# Relay.net
KiCad netlist of a schematic drawn in Altium Designer
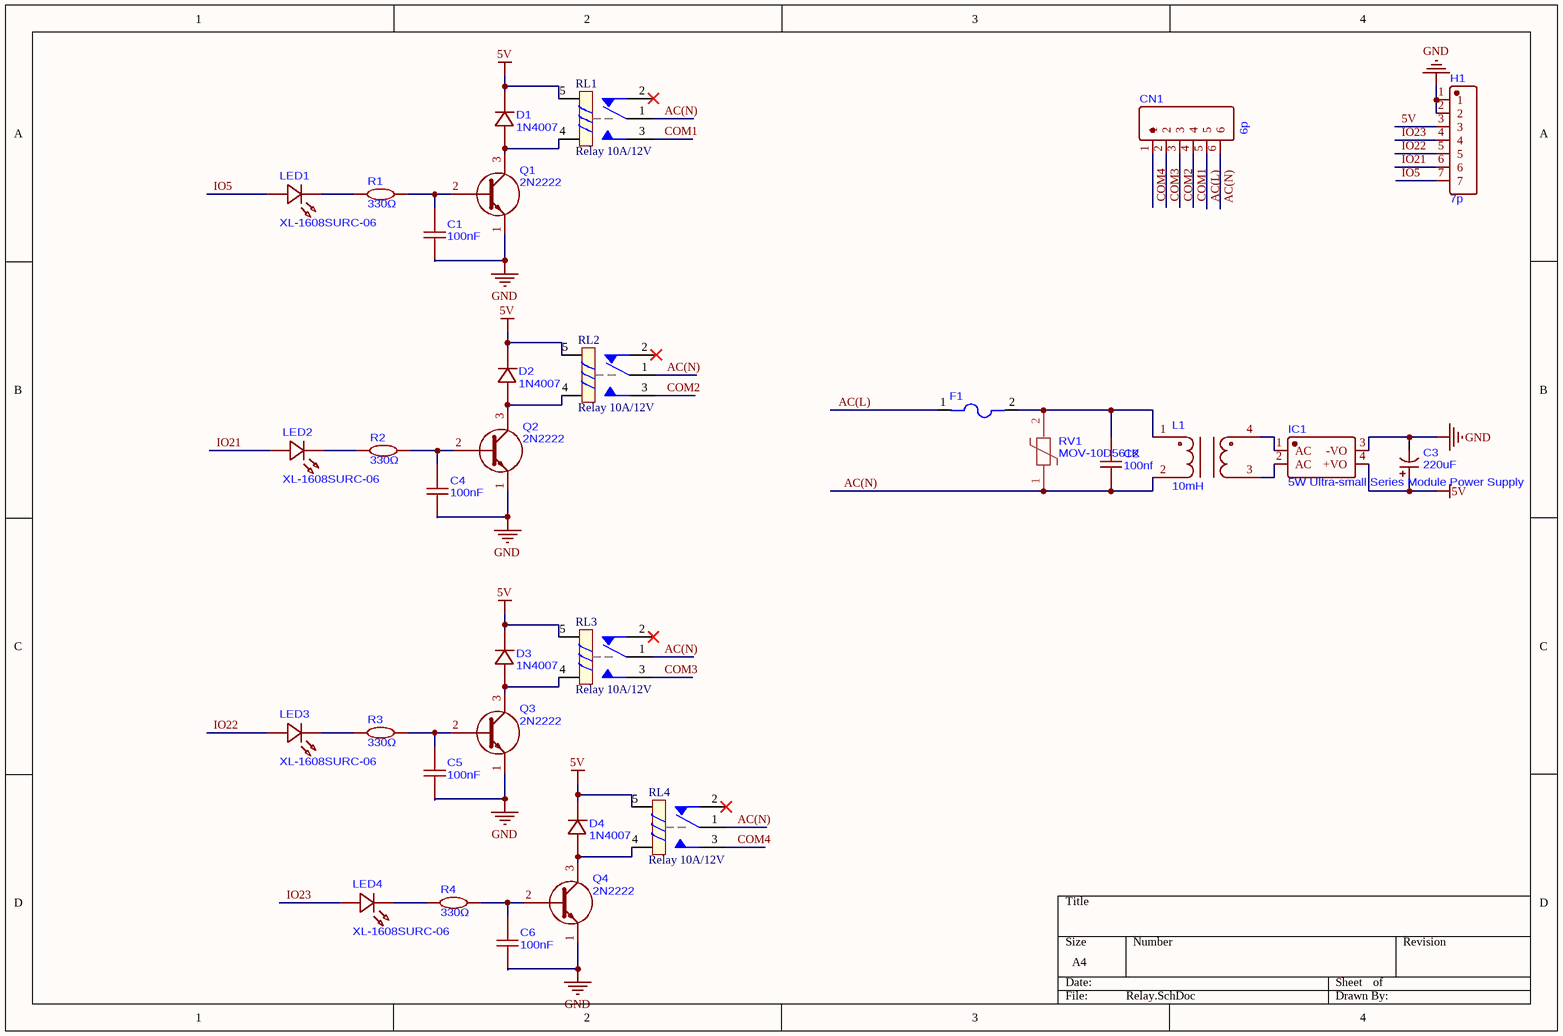
[diagram p0: Relay.SchDoc]

(export (version "E")
  (design (tool "Eeschema 10.0.6"))
  (components
    (comp (ref "C1")
      (value "100nF")
      (footprint "C0603")
      (description "50V 100nF X7R ±10% 0603 Ceramic Capacitors ROHS")
      (libsource (lib "Schlib2") (part "CC0603KRX7R9BB104"))
    )
    (comp (ref "C2")
      (value "100nf")
      (footprint "CAP-TH_L10.0-W5.0-P7.50-D0.6")
      (description "275V 100nF X2 ±10% Through Hole,P=7.5mm Ceramic Capacitors ROHS")
      (libsource (lib "Schlib2") (part "100nF"))
    )
    (comp (ref "C3")
      (value "220uF")
      (footprint "CAP-SMD_BD6.3-L6.6-W6.6-FD")
      (libsource (lib "cap220uF-10V") (part "RVT220UF10V67RV0037"))
    )
    (comp (ref "C4")
      (value "100nF")
      (footprint "C0603")
      (description "50V 100nF X7R ±10% 0603 Ceramic Capacitors ROHS")
      (libsource (lib "Schlib2") (part "CC0603KRX7R9BB104"))
    )
    (comp (ref "C5")
      (value "100nF")
      (footprint "C0603")
      (description "50V 100nF X7R ±10% 0603 Ceramic Capacitors ROHS")
      (libsource (lib "Schlib2") (part "CC0603KRX7R9BB104"))
    )
    (comp (ref "C6")
      (value "100nF")
      (footprint "C0603")
      (description "50V 100nF X7R ±10% 0603 Ceramic Capacitors ROHS")
      (libsource (lib "Schlib2") (part "CC0603KRX7R9BB104"))
    )
    (comp (ref "CN1")
      (value "6p")
      (footprint "CONN-TH_6P-MX128-5.08-GN01-06P-CU-Y-A")
      (libsource (lib "Schlib2") (part "MX128-5.08-GN01-06P-CU-Y-A"))
    )
    (comp (ref "D1")
      (value "1N4007")
      (footprint "DO-41_BD2.4-L4.7-P8.70-D0.9-RD")
      (description "30A 1kV 1.1V@1A 1A DO-41 Single Diodes ROHS")
      (libsource (lib "Schlib2") (part "1N4007"))
    )
    (comp (ref "D2")
      (value "1N4007")
      (footprint "DO-41_BD2.4-L4.7-P8.70-D0.9-RD")
      (description "30A 1kV 1.1V@1A 1A DO-41 Single Diodes ROHS")
      (libsource (lib "Schlib2") (part "1N4007"))
    )
    (comp (ref "D3")
      (value "1N4007")
      (footprint "DO-41_BD2.4-L4.7-P8.70-D0.9-RD")
      (description "30A 1kV 1.1V@1A 1A DO-41 Single Diodes ROHS")
      (libsource (lib "Schlib2") (part "1N4007"))
    )
    (comp (ref "D4")
      (value "1N4007")
      (footprint "DO-41_BD2.4-L4.7-P8.70-D0.9-RD")
      (description "30A 1kV 1.1V@1A 1A DO-41 Single Diodes ROHS")
      (libsource (lib "Schlib2") (part "1N4007"))
    )
    (comp (ref "F1")
      (value "FUSE BRD MNT 1A 250VAC/VDC 2410")
      (footprint "F2410")
      (description "50A Surface Mount Fuse 1A 2410 Fuses ROHS")
      (libsource (lib "Schlib2") (part "JFC2410-1100TS"))
    )
    (comp (ref "H1")
      (value "7p")
      (footprint "CONN-TH_7P-P2.54_XH2.54-7P")
      (libsource (lib "Schlib2") (part "WAFER-XH2.54-7PZZ"))
    )
    (comp (ref "IC1")
      (value "5W Ultra-small Series Module Power Supply")
      (footprint "PWRM-TH_HLK-5M05")
      (description "AC/DC-DC DIP,38x23mm AC DC Converters ROHS")
      (libsource (lib "Schlib2") (part "HLK-5M05"))
    )
    (comp (ref "L1")
      (value "10mH")
      (footprint "FILTER-TH_UU9.8Y-10MH")
      (description "10mH@1kHz 1.2Ω 2 Through Hole Common Mode Chokes ROHS")
      (libsource (lib "Schlib2") (part "UU9.8Y-10MH"))
    )
    (comp (ref "LED1")
      (value "XL-1608SURC-06")
      (footprint "LED0603-RD_RED")
      (description "20mA 2.3V Red 50mW 0603 LED Indication - Discrete ROHS")
      (libsource (lib "Schlib2") (part "XL-1608SURC-06"))
    )
    (comp (ref "LED2")
      (value "XL-1608SURC-06")
      (footprint "LED0603-RD_RED")
      (description "20mA 2.3V Red 50mW 0603 LED Indication - Discrete ROHS")
      (libsource (lib "Schlib2") (part "XL-1608SURC-06"))
    )
    (comp (ref "LED3")
      (value "XL-1608SURC-06")
      (footprint "LED0603-RD_RED")
      (description "20mA 2.3V Red 50mW 0603 LED Indication - Discrete ROHS")
      (libsource (lib "Schlib2") (part "XL-1608SURC-06"))
    )
    (comp (ref "LED4")
      (value "XL-1608SURC-06")
      (footprint "LED0603-RD_RED")
      (description "20mA 2.3V Red 50mW 0603 LED Indication - Discrete ROHS")
      (libsource (lib "Schlib2") (part "XL-1608SURC-06"))
    )
    (comp (ref "Q1")
      (value "2N2222")
      (footprint "2N2222")
      (description "625mW 40V 40@500mA,10V 600mA NPN TO-92 Single Bipolar Transistors ROHS")
      (libsource (lib "Schlib2") (part "2N2222A"))
    )
    (comp (ref "Q2")
      (value "2N2222")
      (footprint "2N2222")
      (description "625mW 40V 40@500mA,10V 600mA NPN TO-92 Single Bipolar Transistors ROHS")
      (libsource (lib "Schlib2") (part "2N2222A"))
    )
    (comp (ref "Q3")
      (value "2N2222")
      (footprint "2N2222")
      (description "625mW 40V 40@500mA,10V 600mA NPN TO-92 Single Bipolar Transistors ROHS")
      (libsource (lib "Schlib2") (part "2N2222A"))
    )
    (comp (ref "Q4")
      (value "2N2222")
      (footprint "2N2222")
      (description "625mW 40V 40@500mA,10V 600mA NPN TO-92 Single Bipolar Transistors ROHS")
      (libsource (lib "Schlib2") (part "2N2222A"))
    )
    (comp (ref "R1")
      (value "330Ω")
      (footprint "R0603")
      (description "100mW 330Ω 75V ±100ppm/℃ Thick Film Resistor ±1% 0603 Chip Resistor - Surface Mount ROHS")
      (libsource (lib "Schlib2") (part "RC0603FR-07330RL"))
    )
    (comp (ref "R2")
      (value "330Ω")
      (footprint "R0603")
      (description "100mW 330Ω 75V ±100ppm/℃ Thick Film Resistor ±1% 0603 Chip Resistor - Surface Mount ROHS")
      (libsource (lib "Schlib2") (part "RC0603FR-07330RL"))
    )
    (comp (ref "R3")
      (value "330Ω")
      (footprint "R0603")
      (description "100mW 330Ω 75V ±100ppm/℃ Thick Film Resistor ±1% 0603 Chip Resistor - Surface Mount ROHS")
      (libsource (lib "Schlib2") (part "RC0603FR-07330RL"))
    )
    (comp (ref "R4")
      (value "330Ω")
      (footprint "R0603")
      (description "100mW 330Ω 75V ±100ppm/℃ Thick Film Resistor ±1% 0603 Chip Resistor - Surface Mount ROHS")
      (libsource (lib "Schlib2") (part "RC0603FR-07330RL"))
    )
    (comp (ref "RL1")
      (value "Relay 10A/12V")
      (footprint "RL_10A_5V")
      (description "Relay SPDT,10A - 5VDC 5 Pin")
      (libsource (lib "Schlib2") (part "Relay 1"))
    )
    (comp (ref "RL2")
      (value "Relay 10A/12V")
      (footprint "RL_10A_5V")
      (description "Relay SPDT,10A - 5VDC 5 Pin")
      (libsource (lib "Schlib2") (part "Relay 1"))
    )
    (comp (ref "RL3")
      (value "Relay 10A/12V")
      (footprint "RL_10A_5V")
      (description "Relay SPDT,10A - 5VDC 5 Pin")
      (libsource (lib "Schlib2") (part "Relay 1"))
    )
    (comp (ref "RL4")
      (value "Relay 10A/12V")
      (footprint "RL_10A_5V")
      (description "Relay SPDT,10A - 5VDC 5 Pin")
      (libsource (lib "Schlib2") (part "Relay 1"))
    )
    (comp (ref "RV1")
      (value "MOV-10D561K")
      (footprint "MOV10D561K")
      (description "925V 460V 350V 560V Through Hole,P=7.5mm Varistors, MOVs ROHS")
      (libsource (lib "Schlib2") (part "MOV-10D561K"))
    )
  )
  (nets
    (net (code "1") (name "/AC(L)") (class "Default")
      (node (ref "CN1") (pin "5") (pinfunction "5_5") (pintype "passive"))
      (node (ref "F1") (pin "1") (pinfunction "1_1") (pintype "passive"))
    )
    (net (code "2") (name "/AC(N)") (class "Default")
      (node (ref "C2") (pin "2") (pinfunction "2_2") (pintype "passive"))
      (node (ref "CN1") (pin "6") (pinfunction "6_6") (pintype "passive"))
      (node (ref "L1") (pin "2") (pinfunction "2_2") (pintype "passive"))
      (node (ref "RL1") (pin "1") (pinfunction "1_1") (pintype "passive"))
      (node (ref "RL2") (pin "1") (pinfunction "1_1") (pintype "passive"))
      (node (ref "RL3") (pin "1") (pinfunction "1_1") (pintype "passive"))
      (node (ref "RL4") (pin "1") (pinfunction "1_1") (pintype "passive"))
      (node (ref "RV1") (pin "1") (pinfunction "1_1") (pintype "passive"))
    )
    (net (code "3") (name "/COM1") (class "Default")
      (node (ref "CN1") (pin "4") (pinfunction "4_4") (pintype "passive"))
      (node (ref "RL1") (pin "3") (pinfunction "3_3") (pintype "passive"))
    )
    (net (code "4") (name "/COM2") (class "Default")
      (node (ref "CN1") (pin "3") (pinfunction "3_3") (pintype "passive"))
      (node (ref "RL2") (pin "3") (pinfunction "3_3") (pintype "passive"))
    )
    (net (code "5") (name "/COM3") (class "Default")
      (node (ref "CN1") (pin "2") (pinfunction "2_2") (pintype "passive"))
      (node (ref "RL3") (pin "3") (pinfunction "3_3") (pintype "passive"))
    )
    (net (code "6") (name "/COM4") (class "Default")
      (node (ref "CN1") (pin "1") (pinfunction "1_1") (pintype "passive"))
      (node (ref "RL4") (pin "3") (pinfunction "3_3") (pintype "passive"))
    )
    (net (code "7") (name "/IO5") (class "Default")
      (node (ref "H1") (pin "7") (pinfunction "7_7") (pintype "passive"))
      (node (ref "LED1") (pin "2") (pinfunction "A_2") (pintype "passive"))
    )
    (net (code "8") (name "/IO21") (class "Default")
      (node (ref "H1") (pin "6") (pinfunction "6_6") (pintype "passive"))
      (node (ref "LED2") (pin "2") (pinfunction "A_2") (pintype "passive"))
    )
    (net (code "9") (name "/IO22") (class "Default")
      (node (ref "H1") (pin "5") (pinfunction "5_5") (pintype "passive"))
      (node (ref "LED3") (pin "2") (pinfunction "A_2") (pintype "passive"))
    )
    (net (code "10") (name "/IO23") (class "Default")
      (node (ref "H1") (pin "4") (pinfunction "4_4") (pintype "passive"))
      (node (ref "LED4") (pin "2") (pinfunction "A_2") (pintype "passive"))
    )
    (net (code "11") (name "5V") (class "Default")
      (node (ref "C3") (pin "1") (pinfunction "1_1") (pintype "passive"))
      (node (ref "D1") (pin "1") (pinfunction "K_1") (pintype "passive"))
      (node (ref "D2") (pin "1") (pinfunction "K_1") (pintype "passive"))
      (node (ref "D3") (pin "1") (pinfunction "K_1") (pintype "passive"))
      (node (ref "D4") (pin "1") (pinfunction "K_1") (pintype "passive"))
      (node (ref "H1") (pin "3") (pinfunction "3_3") (pintype "passive"))
      (node (ref "IC1") (pin "4") (pinfunction "+VO_4") (pintype "passive"))
      (node (ref "RL1") (pin "5") (pinfunction "5_5") (pintype "passive"))
      (node (ref "RL2") (pin "5") (pinfunction "5_5") (pintype "passive"))
      (node (ref "RL3") (pin "5") (pinfunction "5_5") (pintype "passive"))
      (node (ref "RL4") (pin "5") (pinfunction "5_5") (pintype "passive"))
    )
    (net (code "12") (name "GND") (class "Default")
      (node (ref "C1") (pin "1") (pinfunction "1_1") (pintype "passive"))
      (node (ref "C3") (pin "2") (pinfunction "2_2") (pintype "passive"))
      (node (ref "C4") (pin "1") (pinfunction "1_1") (pintype "passive"))
      (node (ref "C5") (pin "1") (pinfunction "1_1") (pintype "passive"))
      (node (ref "C6") (pin "1") (pinfunction "1_1") (pintype "passive"))
      (node (ref "H1") (pin "1") (pinfunction "1_1") (pintype "passive"))
      (node (ref "H1") (pin "2") (pinfunction "2_2") (pintype "passive"))
      (node (ref "IC1") (pin "3") (pinfunction "-VO_3") (pintype "passive"))
      (node (ref "Q1") (pin "1") (pintype "passive"))
      (node (ref "Q2") (pin "1") (pintype "passive"))
      (node (ref "Q3") (pin "1") (pintype "passive"))
      (node (ref "Q4") (pin "1") (pintype "passive"))
    )
    (net (code "13") (name "Net-(C1-Pad2)") (class "Default")
      (node (ref "C1") (pin "2") (pinfunction "2_2") (pintype "passive"))
      (node (ref "Q1") (pin "2") (pintype "passive"))
      (node (ref "R1") (pin "2") (pinfunction "2_2") (pintype "passive"))
    )
    (net (code "14") (name "Net-(C2-Pad1)") (class "Default")
      (node (ref "C2") (pin "1") (pinfunction "1_1") (pintype "passive"))
      (node (ref "F1") (pin "2") (pinfunction "2_2") (pintype "passive"))
      (node (ref "L1") (pin "1") (pinfunction "1_1") (pintype "passive"))
      (node (ref "RV1") (pin "2") (pinfunction "2_2") (pintype "passive"))
    )
    (net (code "15") (name "Net-(C4-Pad2)") (class "Default")
      (node (ref "C4") (pin "2") (pinfunction "2_2") (pintype "passive"))
      (node (ref "Q2") (pin "2") (pintype "passive"))
      (node (ref "R2") (pin "2") (pinfunction "2_2") (pintype "passive"))
    )
    (net (code "16") (name "Net-(C5-Pad2)") (class "Default")
      (node (ref "C5") (pin "2") (pinfunction "2_2") (pintype "passive"))
      (node (ref "Q3") (pin "2") (pintype "passive"))
      (node (ref "R3") (pin "2") (pinfunction "2_2") (pintype "passive"))
    )
    (net (code "17") (name "Net-(C6-Pad2)") (class "Default")
      (node (ref "C6") (pin "2") (pinfunction "2_2") (pintype "passive"))
      (node (ref "Q4") (pin "2") (pintype "passive"))
      (node (ref "R4") (pin "2") (pinfunction "2_2") (pintype "passive"))
    )
    (net (code "18") (name "Net-(D1-A)") (class "Default")
      (node (ref "D1") (pin "2") (pinfunction "A_2") (pintype "passive"))
      (node (ref "Q1") (pin "3") (pintype "passive"))
      (node (ref "RL1") (pin "4") (pinfunction "4_4") (pintype "passive"))
    )
    (net (code "19") (name "Net-(D2-A)") (class "Default")
      (node (ref "D2") (pin "2") (pinfunction "A_2") (pintype "passive"))
      (node (ref "Q2") (pin "3") (pintype "passive"))
      (node (ref "RL2") (pin "4") (pinfunction "4_4") (pintype "passive"))
    )
    (net (code "20") (name "Net-(D3-A)") (class "Default")
      (node (ref "D3") (pin "2") (pinfunction "A_2") (pintype "passive"))
      (node (ref "Q3") (pin "3") (pintype "passive"))
      (node (ref "RL3") (pin "4") (pinfunction "4_4") (pintype "passive"))
    )
    (net (code "21") (name "Net-(D4-A)") (class "Default")
      (node (ref "D4") (pin "2") (pinfunction "A_2") (pintype "passive"))
      (node (ref "Q4") (pin "3") (pintype "passive"))
      (node (ref "RL4") (pin "4") (pinfunction "4_4") (pintype "passive"))
    )
    (net (code "22") (name "Net-(IC1-AC-Pad1)") (class "Default")
      (node (ref "IC1") (pin "1") (pinfunction "AC_1") (pintype "passive"))
      (node (ref "L1") (pin "4") (pinfunction "4_4") (pintype "passive"))
    )
    (net (code "23") (name "Net-(IC1-AC-Pad2)") (class "Default")
      (node (ref "IC1") (pin "2") (pinfunction "AC_2") (pintype "passive"))
      (node (ref "L1") (pin "3") (pinfunction "3_3") (pintype "passive"))
    )
    (net (code "24") (name "Net-(LED1-K)") (class "Default")
      (node (ref "LED1") (pin "1") (pinfunction "K_1") (pintype "passive"))
      (node (ref "R1") (pin "1") (pinfunction "1_1") (pintype "passive"))
    )
    (net (code "25") (name "Net-(LED2-K)") (class "Default")
      (node (ref "LED2") (pin "1") (pinfunction "K_1") (pintype "passive"))
      (node (ref "R2") (pin "1") (pinfunction "1_1") (pintype "passive"))
    )
    (net (code "26") (name "Net-(LED3-K)") (class "Default")
      (node (ref "LED3") (pin "1") (pinfunction "K_1") (pintype "passive"))
      (node (ref "R3") (pin "1") (pinfunction "1_1") (pintype "passive"))
    )
    (net (code "27") (name "Net-(LED4-K)") (class "Default")
      (node (ref "LED4") (pin "1") (pinfunction "K_1") (pintype "passive"))
      (node (ref "R4") (pin "1") (pinfunction "1_1") (pintype "passive"))
    )
    (net (code "28") (name "unconnected-(RL1-Pad2)") (class "Default")
      (node (ref "RL1") (pin "2") (pinfunction "2_2") (pintype "passive+no_connect"))
    )
    (net (code "29") (name "unconnected-(RL2-Pad2)") (class "Default")
      (node (ref "RL2") (pin "2") (pinfunction "2_2") (pintype "passive+no_connect"))
    )
    (net (code "30") (name "unconnected-(RL3-Pad2)") (class "Default")
      (node (ref "RL3") (pin "2") (pinfunction "2_2") (pintype "passive+no_connect"))
    )
    (net (code "31") (name "unconnected-(RL4-Pad2)") (class "Default")
      (node (ref "RL4") (pin "2") (pinfunction "2_2") (pintype "passive+no_connect"))
    )
  )
)
